# fixture.net
KiCad netlist of a schematic drawn in EAGLE
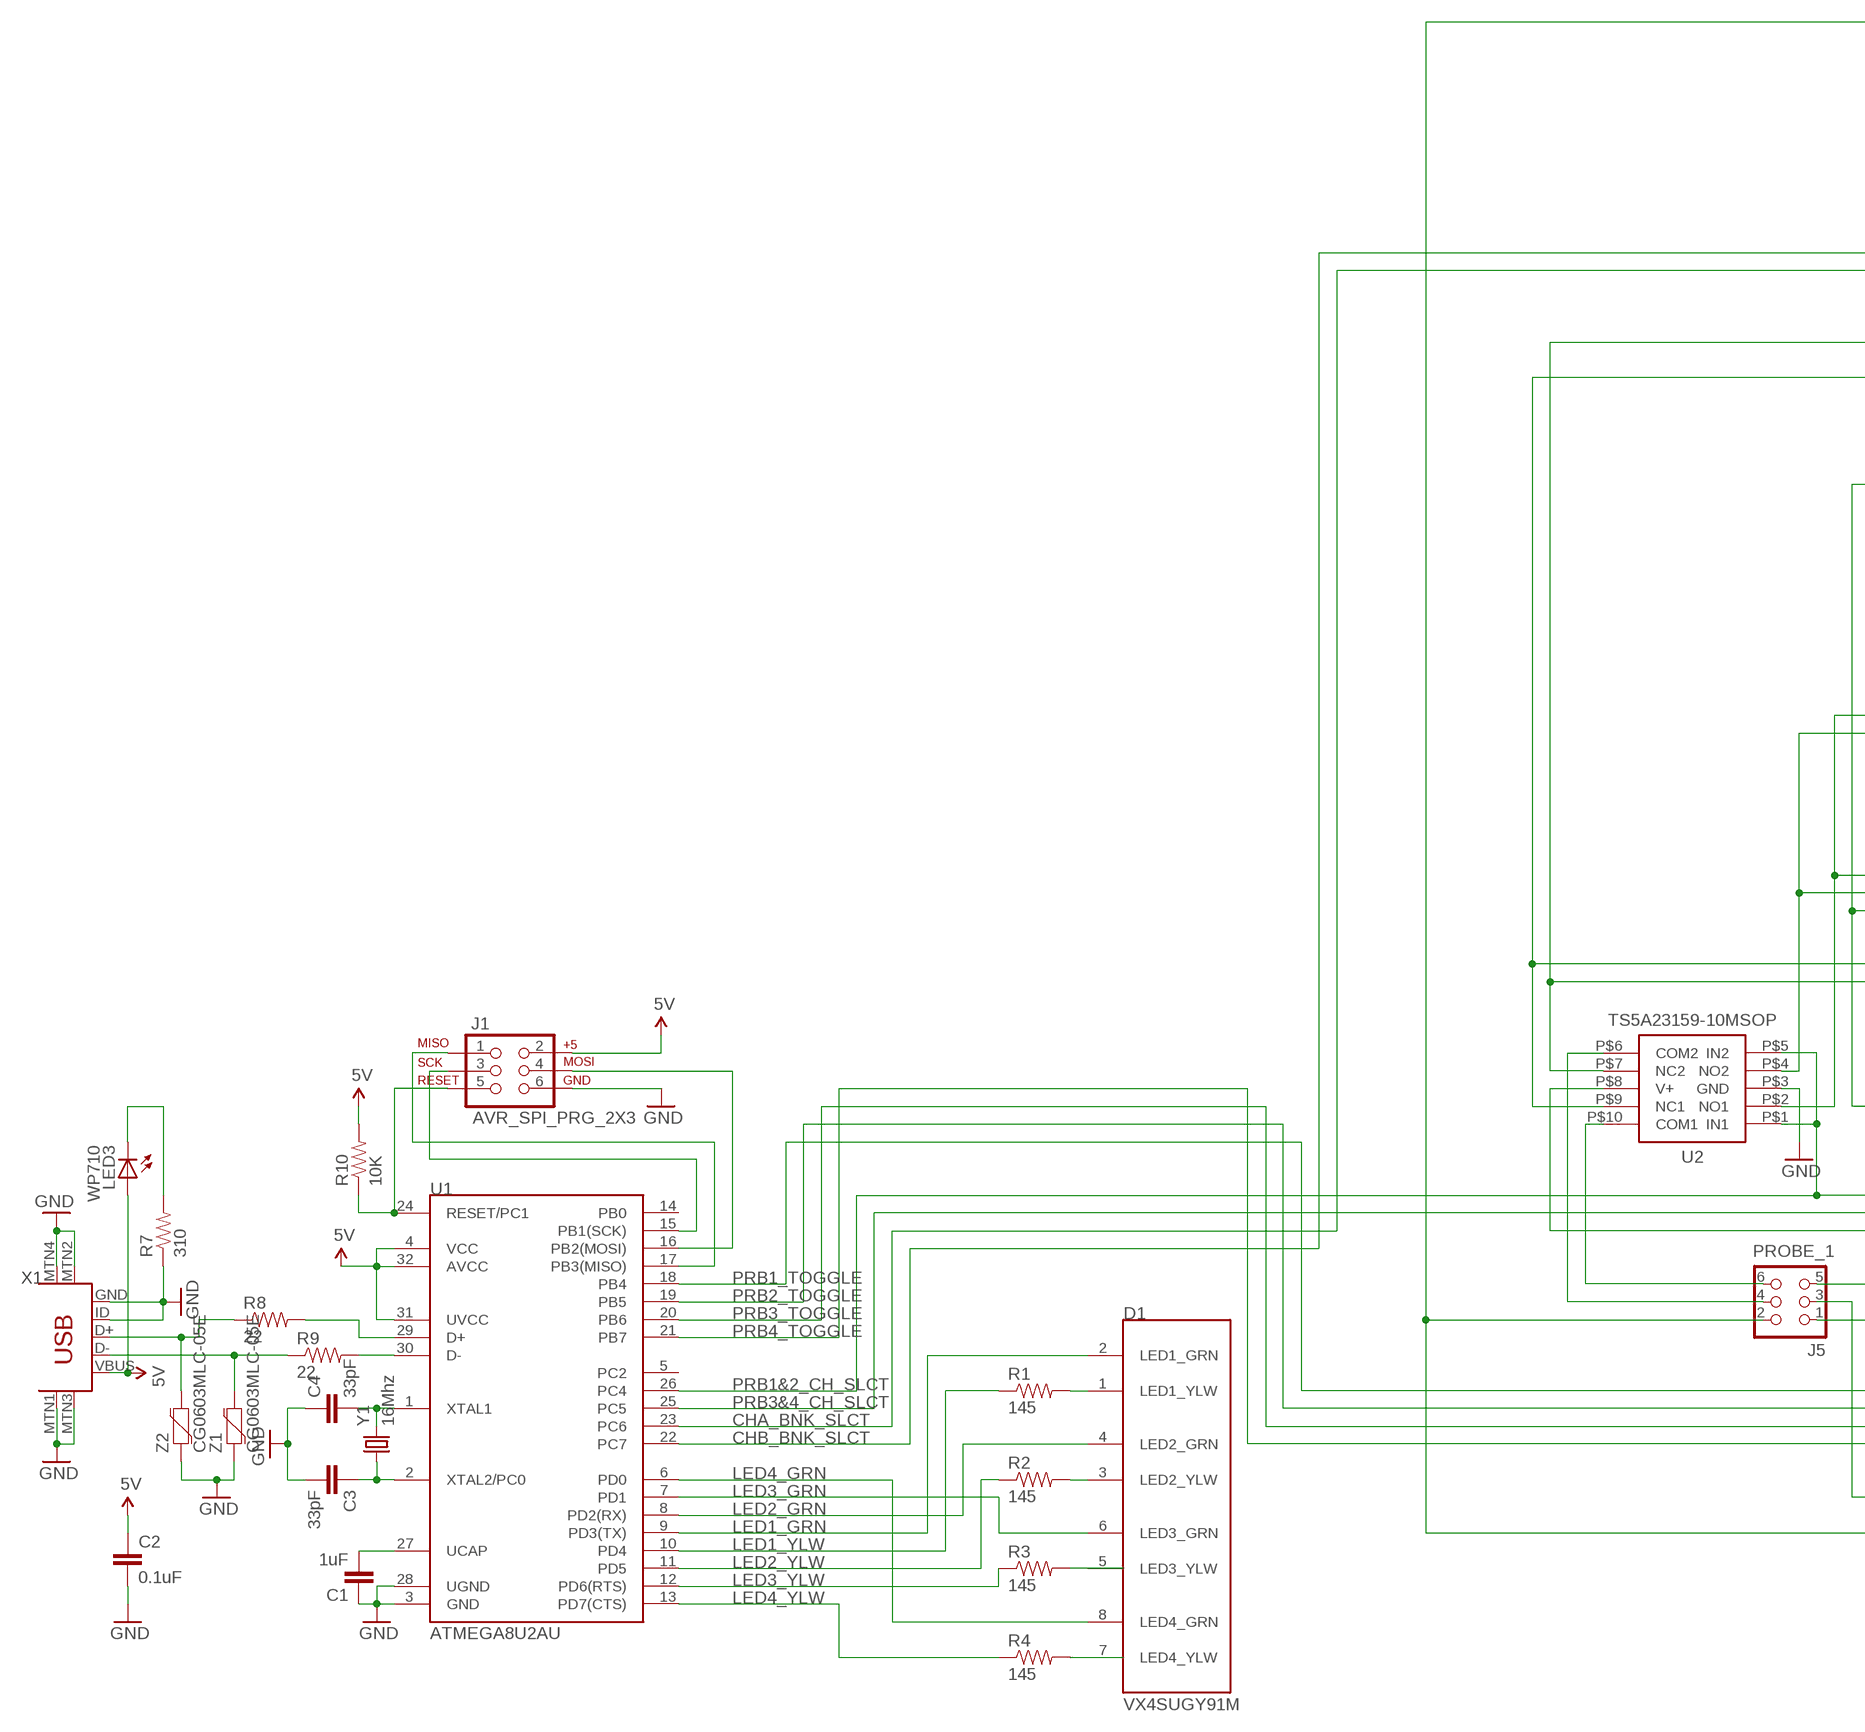
[diagram p0: schematic, sheet 1, part 1 of 2]
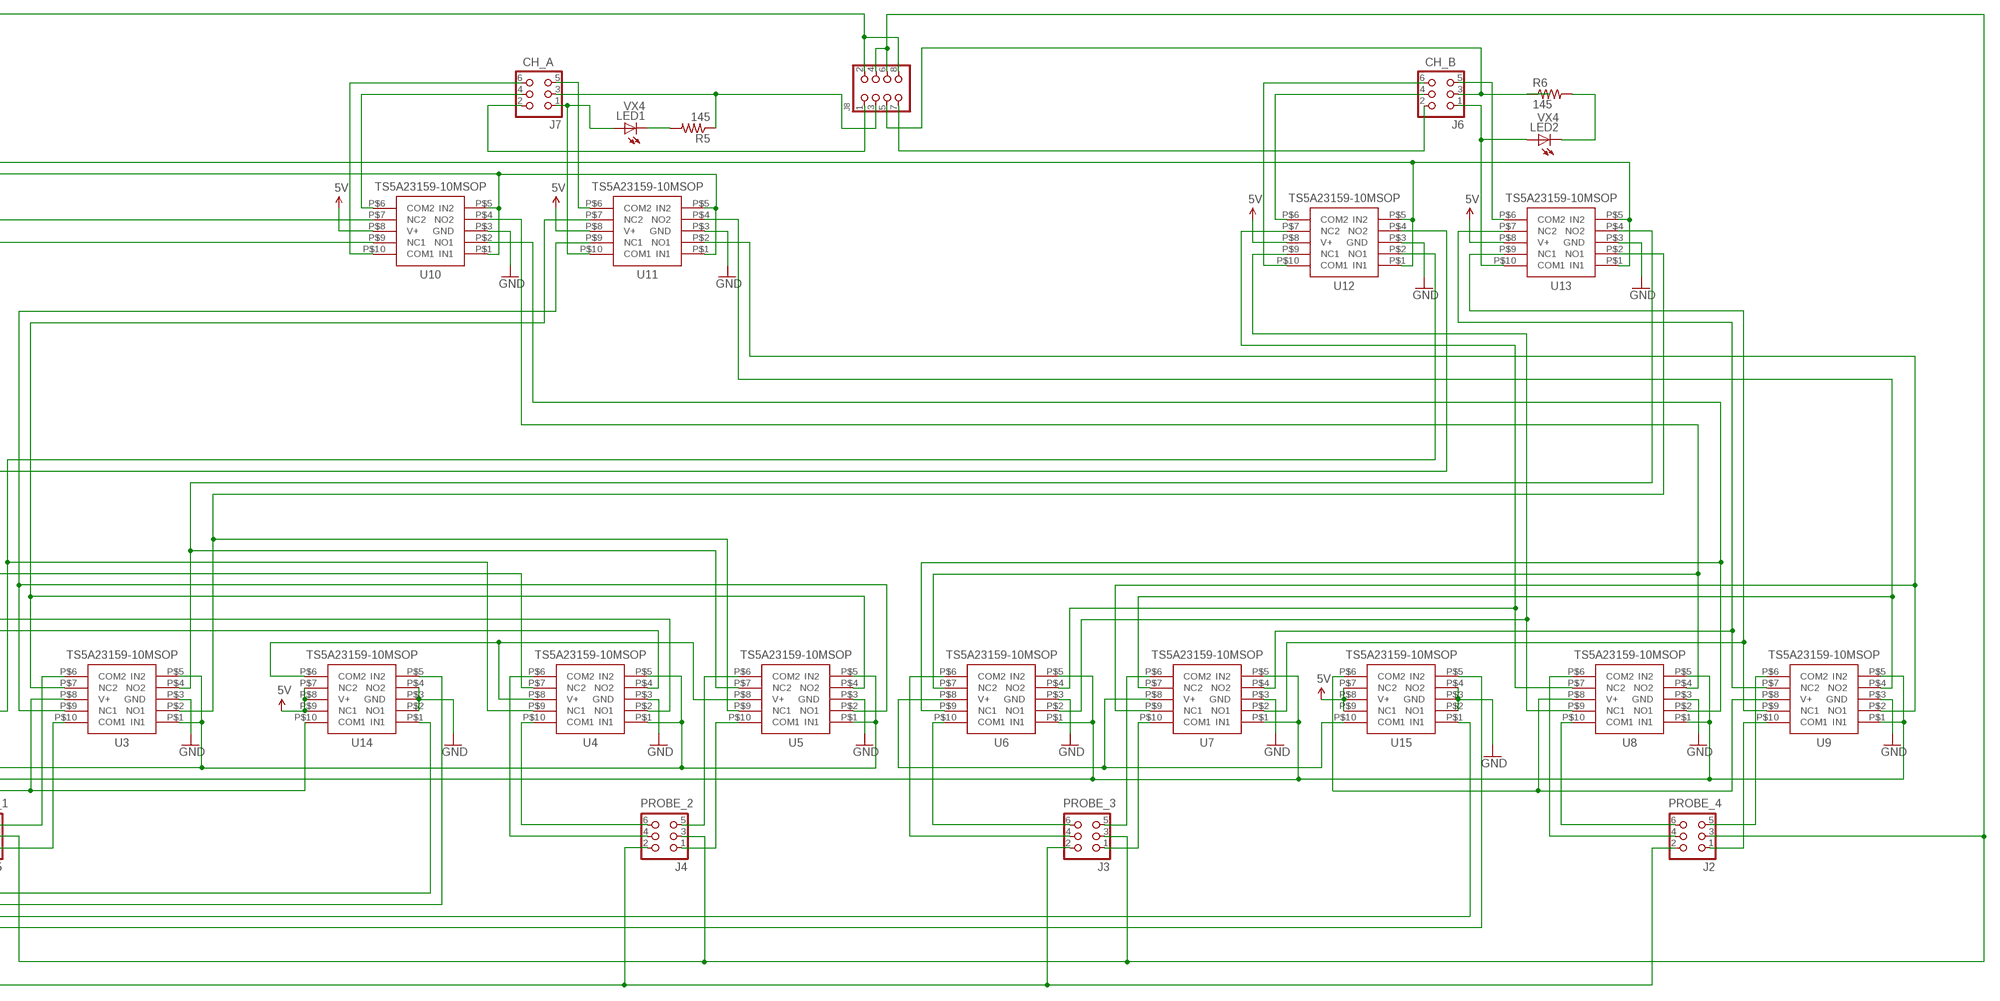
[diagram p1: schematic, sheet 1, part 2 of 2]

(export (version "E")
  (design (tool "Eeschema 10.0.6"))
  (components
    (comp (ref "C1")
      (value "1uF")
      (footprint "eagle-import:0603-CAP")
      (libsource (lib "eagle-import") (part "1.0UF-16V-10%(0603)"))
    )
    (comp (ref "C2")
      (value "0.1uF")
      (footprint "eagle-import:1206")
      (libsource (lib "eagle-import") (part "10UF-6.3V-20%(1206)"))
    )
    (comp (ref "C3")
      (value "33pF")
      (footprint "eagle-import:0603-CAP")
      (libsource (lib "eagle-import") (part "0.1UF-25V(+80/-20%)(0603)"))
    )
    (comp (ref "C4")
      (value "33pF")
      (footprint "eagle-import:0603-CAP")
      (libsource (lib "eagle-import") (part "0.1UF-25V(+80/-20%)(0603)"))
    )
    (comp (ref "D1")
      (value "VX4SUGY91M")
      (footprint "eagle-import:THRU_HOLE")
      (libsource (lib "eagle-import") (part "VX4SUGY91M"))
    )
    (comp (ref "J1")
      (value "AVR_SPI_PRG_2X3")
      (footprint "eagle-import:2X3")
      (libsource (lib "eagle-import") (part "AVR_SPI_PRG_6PTH"))
    )
    (comp (ref "J2")
      (value "CON_HEADER_2X03-PTH")
      (footprint "eagle-import:M2X3")
      (libsource (lib "eagle-import") (part "CON_HEADER_2X03-PTH"))
    )
    (comp (ref "J3")
      (value "CON_HEADER_2X03-PTH")
      (footprint "eagle-import:M2X3")
      (libsource (lib "eagle-import") (part "CON_HEADER_2X03-PTH"))
    )
    (comp (ref "J4")
      (value "CON_HEADER_2X03-PTH")
      (footprint "eagle-import:M2X3")
      (libsource (lib "eagle-import") (part "CON_HEADER_2X03-PTH"))
    )
    (comp (ref "J5")
      (value "CON_HEADER_2X03-PTH")
      (footprint "eagle-import:M2X3")
      (libsource (lib "eagle-import") (part "CON_HEADER_2X03-PTH"))
    )
    (comp (ref "J6")
      (value "CON_HEADER_2X03-PTH")
      (footprint "eagle-import:M2X3")
      (libsource (lib "eagle-import") (part "CON_HEADER_2X03-PTH"))
    )
    (comp (ref "J7")
      (value "CON_HEADER_2X03-PTH")
      (footprint "eagle-import:M2X3")
      (libsource (lib "eagle-import") (part "CON_HEADER_2X03-PTH"))
    )
    (comp (ref "J8")
      (value "CON_HEADER_2X04-PTH")
      (footprint "eagle-import:M2X4")
      (libsource (lib "eagle-import") (part "CON_HEADER_2X04-PTH"))
    )
    (comp (ref "LED1")
      (value "VX4")
      (footprint "eagle-import:LED3MM")
      (libsource (lib "eagle-import") (part "LED3MM"))
    )
    (comp (ref "LED2")
      (value "VX4")
      (footprint "eagle-import:LED3MM")
      (libsource (lib "eagle-import") (part "LED3MM"))
    )
    (comp (ref "LED3")
      (value "WP710")
      (footprint "eagle-import:LED3MM")
      (libsource (lib "eagle-import") (part "LED3MM"))
    )
    (comp (ref "R1")
      (value "145")
      (footprint "eagle-import:0603-RES")
      (libsource (lib "eagle-import") (part "RESISTOR0603-RES"))
    )
    (comp (ref "R2")
      (value "145")
      (footprint "eagle-import:0603-RES")
      (libsource (lib "eagle-import") (part "RESISTOR0603-RES"))
    )
    (comp (ref "R3")
      (value "145")
      (footprint "eagle-import:0603-RES")
      (libsource (lib "eagle-import") (part "RESISTOR0603-RES"))
    )
    (comp (ref "R4")
      (value "145")
      (footprint "eagle-import:0603-RES")
      (libsource (lib "eagle-import") (part "RESISTOR0603-RES"))
    )
    (comp (ref "R5")
      (value "145")
      (footprint "eagle-import:0603-RES")
      (libsource (lib "eagle-import") (part "RESISTOR0603-RES"))
    )
    (comp (ref "R6")
      (value "145")
      (footprint "eagle-import:0603-RES")
      (libsource (lib "eagle-import") (part "RESISTOR0603-RES"))
    )
    (comp (ref "R7")
      (value "310")
      (footprint "eagle-import:0603-RES")
      (libsource (lib "eagle-import") (part "RESISTOR0603-RES"))
    )
    (comp (ref "R8")
      (value "22")
      (footprint "eagle-import:0603-RES")
      (libsource (lib "eagle-import") (part "RESISTOR0603-RES"))
    )
    (comp (ref "R9")
      (value "22")
      (footprint "eagle-import:0603-RES")
      (libsource (lib "eagle-import") (part "RESISTOR0603-RES"))
    )
    (comp (ref "R10")
      (value "10K")
      (footprint "eagle-import:0603-RES")
      (libsource (lib "eagle-import") (part "RESISTOR0603-RES"))
    )
    (comp (ref "U1")
      (value "ATMEGA8U2AU")
      (footprint "eagle-import:TQFP32-08")
      (libsource (lib "eagle-import") (part "ATMEGA8U2AU"))
    )
    (comp (ref "U2")
      (value "TS5A23159-10MSOP")
      (footprint "eagle-import:10MSOP")
      (libsource (lib "eagle-import") (part "TS5A23159-10MSOP"))
    )
    (comp (ref "U3")
      (value "TS5A23159-10MSOP")
      (footprint "eagle-import:10MSOP")
      (libsource (lib "eagle-import") (part "TS5A23159-10MSOP"))
    )
    (comp (ref "U4")
      (value "TS5A23159-10MSOP")
      (footprint "eagle-import:10MSOP")
      (libsource (lib "eagle-import") (part "TS5A23159-10MSOP"))
    )
    (comp (ref "U5")
      (value "TS5A23159-10MSOP")
      (footprint "eagle-import:10MSOP")
      (libsource (lib "eagle-import") (part "TS5A23159-10MSOP"))
    )
    (comp (ref "U6")
      (value "TS5A23159-10MSOP")
      (footprint "eagle-import:10MSOP")
      (libsource (lib "eagle-import") (part "TS5A23159-10MSOP"))
    )
    (comp (ref "U7")
      (value "TS5A23159-10MSOP")
      (footprint "eagle-import:10MSOP")
      (libsource (lib "eagle-import") (part "TS5A23159-10MSOP"))
    )
    (comp (ref "U8")
      (value "TS5A23159-10MSOP")
      (footprint "eagle-import:10MSOP")
      (libsource (lib "eagle-import") (part "TS5A23159-10MSOP"))
    )
    (comp (ref "U9")
      (value "TS5A23159-10MSOP")
      (footprint "eagle-import:10MSOP")
      (libsource (lib "eagle-import") (part "TS5A23159-10MSOP"))
    )
    (comp (ref "U10")
      (value "TS5A23159-10MSOP")
      (footprint "eagle-import:10MSOP")
      (libsource (lib "eagle-import") (part "TS5A23159-10MSOP"))
    )
    (comp (ref "U11")
      (value "TS5A23159-10MSOP")
      (footprint "eagle-import:10MSOP")
      (libsource (lib "eagle-import") (part "TS5A23159-10MSOP"))
    )
    (comp (ref "U12")
      (value "TS5A23159-10MSOP")
      (footprint "eagle-import:10MSOP")
      (libsource (lib "eagle-import") (part "TS5A23159-10MSOP"))
    )
    (comp (ref "U13")
      (value "TS5A23159-10MSOP")
      (footprint "eagle-import:10MSOP")
      (libsource (lib "eagle-import") (part "TS5A23159-10MSOP"))
    )
    (comp (ref "U14")
      (value "TS5A23159-10MSOP")
      (footprint "eagle-import:10MSOP")
      (libsource (lib "eagle-import") (part "TS5A23159-10MSOP"))
    )
    (comp (ref "U15")
      (value "TS5A23159-10MSOP")
      (footprint "eagle-import:10MSOP")
      (libsource (lib "eagle-import") (part "TS5A23159-10MSOP"))
    )
    (comp (ref "X1")
      (value "USB-MINIB-5PIN")
      (footprint "eagle-import:USB-MINIB")
      (libsource (lib "eagle-import") (part "USB-MINIB-5PIN"))
    )
    (comp (ref "Y1")
      (value "16Mhz")
      (footprint "eagle-import:HC49US")
      (libsource (lib "eagle-import") (part "CRYSTALHC49US"))
    )
    (comp (ref "Z1")
      (value "CG0603MLC-05E")
      (footprint "eagle-import:0603-RES")
      (libsource (lib "eagle-import") (part "VARISTOR-0603"))
    )
    (comp (ref "Z2")
      (value "CG0603MLC-05E")
      (footprint "eagle-import:0603-RES")
      (libsource (lib "eagle-import") (part "VARISTOR-0603"))
    )
  )
  (nets
    (net (code "1") (name "/CHA_BNK_SLCT") (class "Default")
      (node (ref "U1") (pin "23") (pinfunction "PC6_23") (pintype "bidirectional"))
      (node (ref "U10") (pin "P$1") (pinfunction "IN1_P$1") (pintype "input"))
      (node (ref "U10") (pin "P$5") (pinfunction "IN2_P$5") (pintype "input"))
      (node (ref "U11") (pin "P$1") (pinfunction "IN1_P$1") (pintype "input"))
      (node (ref "U11") (pin "P$5") (pinfunction "IN2_P$5") (pintype "input"))
    )
    (net (code "2") (name "/CHB_BNK_SLCT") (class "Default")
      (node (ref "U1") (pin "22") (pinfunction "PC7_22") (pintype "bidirectional"))
      (node (ref "U12") (pin "P$1") (pinfunction "IN1_P$1") (pintype "input"))
      (node (ref "U12") (pin "P$5") (pinfunction "IN2_P$5") (pintype "input"))
      (node (ref "U13") (pin "P$1") (pinfunction "IN1_P$1") (pintype "input"))
      (node (ref "U13") (pin "P$5") (pinfunction "IN2_P$5") (pintype "input"))
    )
    (net (code "3") (name "/LED1_GRN") (class "Default")
      (node (ref "D1") (pin "2") (pinfunction "LED1_GRN_2") (pintype "bidirectional"))
      (node (ref "U1") (pin "9") (pinfunction "PD3(TX)_9") (pintype "bidirectional"))
    )
    (net (code "4") (name "/LED1_YLW") (class "Default")
      (node (ref "R1") (pin "1") (pinfunction "1_1") (pintype "passive"))
      (node (ref "U1") (pin "10") (pinfunction "PD4_10") (pintype "bidirectional"))
    )
    (net (code "5") (name "/LED2_GRN") (class "Default")
      (node (ref "D1") (pin "4") (pinfunction "LED2_GRN_4") (pintype "bidirectional"))
      (node (ref "U1") (pin "8") (pinfunction "PD2(RX)_8") (pintype "bidirectional"))
    )
    (net (code "6") (name "/LED2_YLW") (class "Default")
      (node (ref "R2") (pin "1") (pinfunction "1_1") (pintype "passive"))
      (node (ref "U1") (pin "11") (pinfunction "PD5_11") (pintype "bidirectional"))
    )
    (net (code "7") (name "/LED3_GRN") (class "Default")
      (node (ref "D1") (pin "6") (pinfunction "LED3_GRN_6") (pintype "bidirectional"))
      (node (ref "U1") (pin "7") (pinfunction "PD1_7") (pintype "bidirectional"))
    )
    (net (code "8") (name "/LED3_YLW") (class "Default")
      (node (ref "R3") (pin "1") (pinfunction "1_1") (pintype "passive"))
      (node (ref "U1") (pin "12") (pinfunction "PD6(RTS)_12") (pintype "bidirectional"))
    )
    (net (code "9") (name "/LED4_GRN") (class "Default")
      (node (ref "D1") (pin "8") (pinfunction "LED4_GRN_8") (pintype "bidirectional"))
      (node (ref "U1") (pin "6") (pinfunction "PD0_6") (pintype "bidirectional"))
    )
    (net (code "10") (name "/LED4_YLW") (class "Default")
      (node (ref "R4") (pin "1") (pinfunction "1_1") (pintype "passive"))
      (node (ref "U1") (pin "13") (pinfunction "PD7(CTS)_13") (pintype "bidirectional"))
    )
    (net (code "11") (name "/PRB1&2_CH_SLCT") (class "Default")
      (node (ref "U1") (pin "26") (pinfunction "PC4_26") (pintype "bidirectional"))
      (node (ref "U2") (pin "P$1") (pinfunction "IN1_P$1") (pintype "input"))
      (node (ref "U2") (pin "P$5") (pinfunction "IN2_P$5") (pintype "input"))
      (node (ref "U3") (pin "P$1") (pinfunction "IN1_P$1") (pintype "input"))
      (node (ref "U3") (pin "P$5") (pinfunction "IN2_P$5") (pintype "input"))
      (node (ref "U4") (pin "P$1") (pinfunction "IN1_P$1") (pintype "input"))
      (node (ref "U4") (pin "P$5") (pinfunction "IN2_P$5") (pintype "input"))
      (node (ref "U5") (pin "P$1") (pinfunction "IN1_P$1") (pintype "input"))
      (node (ref "U5") (pin "P$5") (pinfunction "IN2_P$5") (pintype "input"))
    )
    (net (code "12") (name "/PRB1_TOGGLE") (class "Default")
      (node (ref "U1") (pin "18") (pinfunction "PB4_18") (pintype "bidirectional"))
      (node (ref "U14") (pin "P$1") (pinfunction "IN1_P$1") (pintype "input"))
    )
    (net (code "13") (name "/PRB2_TOGGLE") (class "Default")
      (node (ref "U1") (pin "19") (pinfunction "PB5_19") (pintype "bidirectional"))
      (node (ref "U14") (pin "P$5") (pinfunction "IN2_P$5") (pintype "input"))
    )
    (net (code "14") (name "/PRB3&4_CH_SLCT") (class "Default")
      (node (ref "U1") (pin "25") (pinfunction "PC5_25") (pintype "bidirectional"))
      (node (ref "U6") (pin "P$1") (pinfunction "IN1_P$1") (pintype "input"))
      (node (ref "U6") (pin "P$5") (pinfunction "IN2_P$5") (pintype "input"))
      (node (ref "U7") (pin "P$1") (pinfunction "IN1_P$1") (pintype "input"))
      (node (ref "U7") (pin "P$5") (pinfunction "IN2_P$5") (pintype "input"))
      (node (ref "U8") (pin "P$1") (pinfunction "IN1_P$1") (pintype "input"))
      (node (ref "U8") (pin "P$5") (pinfunction "IN2_P$5") (pintype "input"))
      (node (ref "U9") (pin "P$1") (pinfunction "IN1_P$1") (pintype "input"))
      (node (ref "U9") (pin "P$5") (pinfunction "IN2_P$5") (pintype "input"))
    )
    (net (code "15") (name "/PRB3_TOGGLE") (class "Default")
      (node (ref "U1") (pin "20") (pinfunction "PB6_20") (pintype "bidirectional"))
      (node (ref "U15") (pin "P$1") (pinfunction "IN1_P$1") (pintype "input"))
    )
    (net (code "16") (name "/PRB4_TOGGLE") (class "Default")
      (node (ref "U1") (pin "21") (pinfunction "PB7_21") (pintype "bidirectional"))
      (node (ref "U15") (pin "P$5") (pinfunction "IN2_P$5") (pintype "input"))
    )
    (net (code "17") (name "5V") (class "Default")
      (node (ref "C2") (pin "1") (pinfunction "1_1") (pintype "passive"))
      (node (ref "J1") (pin "2") (pinfunction "2_2") (pintype "passive"))
      (node (ref "LED3") (pin "A") (pinfunction "A_A") (pintype "passive"))
      (node (ref "R10") (pin "2") (pinfunction "2_2") (pintype "passive"))
      (node (ref "U1") (pin "31") (pinfunction "UVCC_31") (pintype "bidirectional"))
      (node (ref "U1") (pin "32") (pinfunction "AVCC_32") (pintype "bidirectional"))
      (node (ref "U1") (pin "4") (pinfunction "VCC_4") (pintype "bidirectional"))
      (node (ref "U10") (pin "P$8") (pinfunction "V+_P$8") (pintype "power_in"))
      (node (ref "U11") (pin "P$8") (pinfunction "V+_P$8") (pintype "power_in"))
      (node (ref "U12") (pin "P$8") (pinfunction "V+_P$8") (pintype "power_in"))
      (node (ref "U13") (pin "P$8") (pinfunction "V+_P$8") (pintype "power_in"))
      (node (ref "U14") (pin "P$7") (pinfunction "NC2_P$7") (pintype "bidirectional"))
      (node (ref "U14") (pin "P$8") (pinfunction "V+_P$8") (pintype "power_in"))
      (node (ref "U14") (pin "P$9") (pinfunction "NC1_P$9") (pintype "bidirectional"))
      (node (ref "U15") (pin "P$7") (pinfunction "NC2_P$7") (pintype "bidirectional"))
      (node (ref "U15") (pin "P$8") (pinfunction "V+_P$8") (pintype "power_in"))
      (node (ref "U15") (pin "P$9") (pinfunction "NC1_P$9") (pintype "bidirectional"))
      (node (ref "X1") (pin "VBUS") (pinfunction "VBUS_VBUS") (pintype "bidirectional"))
    )
    (net (code "18") (name "GND") (class "Default")
      (node (ref "C1") (pin "1") (pinfunction "1_1") (pintype "passive"))
      (node (ref "C2") (pin "2") (pinfunction "2_2") (pintype "passive"))
      (node (ref "C3") (pin "2") (pinfunction "2_2") (pintype "passive"))
      (node (ref "C4") (pin "1") (pinfunction "1_1") (pintype "passive"))
      (node (ref "J1") (pin "6") (pinfunction "6_6") (pintype "passive"))
      (node (ref "R7") (pin "1") (pinfunction "1_1") (pintype "passive"))
      (node (ref "U1") (pin "28") (pinfunction "UGND_28") (pintype "bidirectional"))
      (node (ref "U1") (pin "3") (pinfunction "GND_3") (pintype "bidirectional"))
      (node (ref "U10") (pin "P$3") (pinfunction "GND_P$3") (pintype "power_in"))
      (node (ref "U11") (pin "P$3") (pinfunction "GND_P$3") (pintype "power_in"))
      (node (ref "U12") (pin "P$3") (pinfunction "GND_P$3") (pintype "power_in"))
      (node (ref "U13") (pin "P$3") (pinfunction "GND_P$3") (pintype "power_in"))
      (node (ref "U14") (pin "P$2") (pinfunction "NO1_P$2") (pintype "bidirectional"))
      (node (ref "U14") (pin "P$3") (pinfunction "GND_P$3") (pintype "power_in"))
      (node (ref "U14") (pin "P$4") (pinfunction "NO2_P$4") (pintype "bidirectional"))
      (node (ref "U15") (pin "P$2") (pinfunction "NO1_P$2") (pintype "bidirectional"))
      (node (ref "U15") (pin "P$3") (pinfunction "GND_P$3") (pintype "power_in"))
      (node (ref "U15") (pin "P$4") (pinfunction "NO2_P$4") (pintype "bidirectional"))
      (node (ref "U2") (pin "P$3") (pinfunction "GND_P$3") (pintype "power_in"))
      (node (ref "U3") (pin "P$3") (pinfunction "GND_P$3") (pintype "power_in"))
      (node (ref "U4") (pin "P$3") (pinfunction "GND_P$3") (pintype "power_in"))
      (node (ref "U5") (pin "P$3") (pinfunction "GND_P$3") (pintype "power_in"))
      (node (ref "U6") (pin "P$3") (pinfunction "GND_P$3") (pintype "power_in"))
      (node (ref "U7") (pin "P$3") (pinfunction "GND_P$3") (pintype "power_in"))
      (node (ref "U8") (pin "P$3") (pinfunction "GND_P$3") (pintype "power_in"))
      (node (ref "U9") (pin "P$3") (pinfunction "GND_P$3") (pintype "power_in"))
      (node (ref "X1") (pin "GND") (pinfunction "GND_GND") (pintype "bidirectional"))
      (node (ref "X1") (pin "ID") (pinfunction "ID_ID") (pintype "bidirectional"))
      (node (ref "X1") (pin "MTN1") (pinfunction "MTN2_MTN1") (pintype "bidirectional"))
      (node (ref "X1") (pin "MTN2") (pinfunction "MTN3_MTN2") (pintype "bidirectional"))
      (node (ref "X1") (pin "MTN3") (pinfunction "MTN1_MTN3") (pintype "bidirectional"))
      (node (ref "X1") (pin "MTN4") (pinfunction "MTN4_MTN4") (pintype "bidirectional"))
      (node (ref "Z1") (pin "1") (pinfunction "1_1") (pintype "passive"))
      (node (ref "Z2") (pin "1") (pinfunction "1_1") (pintype "passive"))
    )
    (net (code "19") (name "Net-(D1-LED1_YLW)") (class "Default")
      (node (ref "D1") (pin "1") (pinfunction "LED1_YLW_1") (pintype "bidirectional"))
      (node (ref "R1") (pin "2") (pinfunction "2_2") (pintype "passive"))
    )
    (net (code "20") (name "Net-(D1-LED2_YLW)") (class "Default")
      (node (ref "D1") (pin "3") (pinfunction "LED2_YLW_3") (pintype "bidirectional"))
      (node (ref "R2") (pin "2") (pinfunction "2_2") (pintype "passive"))
    )
    (net (code "21") (name "Net-(D1-LED3_YLW)") (class "Default")
      (node (ref "D1") (pin "5") (pinfunction "LED3_YLW_5") (pintype "bidirectional"))
      (node (ref "R3") (pin "2") (pinfunction "2_2") (pintype "passive"))
    )
    (net (code "22") (name "Net-(D1-LED4_YLW)") (class "Default")
      (node (ref "D1") (pin "7") (pinfunction "LED4_YLW_7") (pintype "bidirectional"))
      (node (ref "R4") (pin "2") (pinfunction "2_2") (pintype "passive"))
    )
    (net (code "23") (name "Net-(J8-P$1)") (class "Default")
      (node (ref "J7") (pin "2") (pinfunction "2_2") (pintype "passive"))
      (node (ref "J8") (pin "1") (pinfunction "P$1_1") (pintype "passive"))
    )
    (net (code "24") (name "Net-(J8-P$2)") (class "Default")
      (node (ref "J2") (pin "2") (pinfunction "2_2") (pintype "passive"))
      (node (ref "J3") (pin "2") (pinfunction "2_2") (pintype "passive"))
      (node (ref "J4") (pin "2") (pinfunction "2_2") (pintype "passive"))
      (node (ref "J5") (pin "2") (pinfunction "2_2") (pintype "passive"))
      (node (ref "J8") (pin "2") (pinfunction "P$2_2") (pintype "passive"))
      (node (ref "J8") (pin "8") (pinfunction "P$8_8") (pintype "passive"))
    )
    (net (code "25") (name "Net-(J8-P$3)") (class "Default")
      (node (ref "J7") (pin "3") (pinfunction "3_3") (pintype "passive"))
      (node (ref "J8") (pin "3") (pinfunction "P$3_3") (pintype "passive"))
      (node (ref "R5") (pin "1") (pinfunction "1_1") (pintype "passive"))
    )
    (net (code "26") (name "Net-(J8-P$4)") (class "Default")
      (node (ref "J2") (pin "3") (pinfunction "3_3") (pintype "passive"))
      (node (ref "J3") (pin "3") (pinfunction "3_3") (pintype "passive"))
      (node (ref "J4") (pin "3") (pinfunction "3_3") (pintype "passive"))
      (node (ref "J5") (pin "3") (pinfunction "3_3") (pintype "passive"))
      (node (ref "J8") (pin "4") (pinfunction "P$4_4") (pintype "passive"))
      (node (ref "J8") (pin "6") (pinfunction "P$6_6") (pintype "passive"))
    )
    (net (code "27") (name "Net-(J8-P$5)") (class "Default")
      (node (ref "J6") (pin "3") (pinfunction "3_3") (pintype "passive"))
      (node (ref "J8") (pin "5") (pinfunction "P$5_5") (pintype "passive"))
      (node (ref "R6") (pin "1") (pinfunction "1_1") (pintype "passive"))
    )
    (net (code "28") (name "Net-(J8-P$7)") (class "Default")
      (node (ref "J6") (pin "2") (pinfunction "2_2") (pintype "passive"))
      (node (ref "J8") (pin "7") (pinfunction "P$7_7") (pintype "passive"))
    )
    (net (code "29") (name "Net-(LED1-C)") (class "Default")
      (node (ref "LED1") (pin "K") (pinfunction "C_K") (pintype "passive"))
      (node (ref "R5") (pin "2") (pinfunction "2_2") (pintype "passive"))
    )
    (net (code "30") (name "Net-(LED2-C)") (class "Default")
      (node (ref "LED2") (pin "K") (pinfunction "C_K") (pintype "passive"))
      (node (ref "R6") (pin "2") (pinfunction "2_2") (pintype "passive"))
    )
    (net (code "31") (name "Net-(LED3-C)") (class "Default")
      (node (ref "LED3") (pin "K") (pinfunction "C_K") (pintype "passive"))
      (node (ref "R7") (pin "2") (pinfunction "2_2") (pintype "passive"))
    )
    (net (code "32") (name "Net-(R8-Pad1)") (class "Default")
      (node (ref "R8") (pin "1") (pinfunction "1_1") (pintype "passive"))
      (node (ref "X1") (pin "D+") (pinfunction "D+_D+") (pintype "bidirectional"))
      (node (ref "Z2") (pin "2") (pinfunction "2_2") (pintype "passive"))
    )
    (net (code "33") (name "Net-(R9-Pad1)") (class "Default")
      (node (ref "R9") (pin "1") (pinfunction "1_1") (pintype "passive"))
      (node (ref "X1") (pin "D-") (pinfunction "D-_D-") (pintype "bidirectional"))
      (node (ref "Z1") (pin "2") (pinfunction "2_2") (pintype "passive"))
    )
    (net (code "34") (name "Net-(U1-D+)") (class "Default")
      (node (ref "R8") (pin "2") (pinfunction "2_2") (pintype "passive"))
      (node (ref "U1") (pin "29") (pinfunction "D+_29") (pintype "bidirectional"))
    )
    (net (code "35") (name "Net-(U1-D-)") (class "Default")
      (node (ref "R9") (pin "2") (pinfunction "2_2") (pintype "passive"))
      (node (ref "U1") (pin "30") (pinfunction "D-_30") (pintype "bidirectional"))
    )
    (net (code "36") (name "Net-(U1-PB1(SCK))") (class "Default")
      (node (ref "J1") (pin "3") (pinfunction "3_3") (pintype "passive"))
      (node (ref "U1") (pin "15") (pinfunction "PB1(SCK)_15") (pintype "bidirectional"))
    )
    (net (code "37") (name "Net-(U1-PB2(MOSI))") (class "Default")
      (node (ref "J1") (pin "4") (pinfunction "4_4") (pintype "passive"))
      (node (ref "U1") (pin "16") (pinfunction "PB2(MOSI)_16") (pintype "bidirectional"))
    )
    (net (code "38") (name "Net-(U1-PB3(MISO))") (class "Default")
      (node (ref "J1") (pin "1") (pinfunction "1_1") (pintype "passive"))
      (node (ref "U1") (pin "17") (pinfunction "PB3(MISO)_17") (pintype "bidirectional"))
    )
    (net (code "39") (name "Net-(U1-RESET{slash}PC1)") (class "Default")
      (node (ref "J1") (pin "5") (pinfunction "5_5") (pintype "passive"))
      (node (ref "R10") (pin "1") (pinfunction "1_1") (pintype "passive"))
      (node (ref "U1") (pin "24") (pinfunction "RESET/PC1_24") (pintype "bidirectional"))
    )
    (net (code "40") (name "Net-(U1-UCAP)") (class "Default")
      (node (ref "C1") (pin "2") (pinfunction "2_2") (pintype "passive"))
      (node (ref "U1") (pin "27") (pinfunction "UCAP_27") (pintype "bidirectional"))
    )
    (net (code "41") (name "Net-(U1-XTAL1)") (class "Default")
      (node (ref "C4") (pin "2") (pinfunction "2_2") (pintype "passive"))
      (node (ref "U1") (pin "1") (pinfunction "XTAL1_1") (pintype "bidirectional"))
      (node (ref "Y1") (pin "2") (pinfunction "2_2") (pintype "passive"))
    )
    (net (code "42") (name "Net-(U1-XTAL2{slash}PC0)") (class "Default")
      (node (ref "C3") (pin "1") (pinfunction "1_1") (pintype "passive"))
      (node (ref "U1") (pin "2") (pinfunction "XTAL2/PC0_2") (pintype "bidirectional"))
      (node (ref "Y1") (pin "1") (pinfunction "1_1") (pintype "passive"))
    )
    (net (code "43") (name "Net-(U2-COM1)") (class "Default")
      (node (ref "J5") (pin "6") (pinfunction "6_6") (pintype "passive"))
      (node (ref "U2") (pin "P$10") (pinfunction "COM1_P$10") (pintype "bidirectional"))
    )
    (net (code "44") (name "Net-(U2-COM2)") (class "Default")
      (node (ref "J5") (pin "4") (pinfunction "4_4") (pintype "passive"))
      (node (ref "U2") (pin "P$6") (pinfunction "COM2_P$6") (pintype "bidirectional"))
    )
    (net (code "45") (name "Net-(U3-COM1)") (class "Default")
      (node (ref "J5") (pin "1") (pinfunction "1_1") (pintype "passive"))
      (node (ref "U3") (pin "P$10") (pinfunction "COM1_P$10") (pintype "bidirectional"))
    )
    (net (code "46") (name "Net-(U3-COM2)") (class "Default")
      (node (ref "J5") (pin "5") (pinfunction "5_5") (pintype "passive"))
      (node (ref "U3") (pin "P$6") (pinfunction "COM2_P$6") (pintype "bidirectional"))
    )
    (net (code "47") (name "Net-(U4-COM1)") (class "Default")
      (node (ref "J4") (pin "6") (pinfunction "6_6") (pintype "passive"))
      (node (ref "U4") (pin "P$10") (pinfunction "COM1_P$10") (pintype "bidirectional"))
    )
    (net (code "48") (name "Net-(U4-COM2)") (class "Default")
      (node (ref "J4") (pin "4") (pinfunction "4_4") (pintype "passive"))
      (node (ref "U4") (pin "P$6") (pinfunction "COM2_P$6") (pintype "bidirectional"))
    )
    (net (code "49") (name "Net-(U5-COM1)") (class "Default")
      (node (ref "J4") (pin "1") (pinfunction "1_1") (pintype "passive"))
      (node (ref "U5") (pin "P$10") (pinfunction "COM1_P$10") (pintype "bidirectional"))
    )
    (net (code "50") (name "Net-(U5-COM2)") (class "Default")
      (node (ref "J4") (pin "5") (pinfunction "5_5") (pintype "passive"))
      (node (ref "U5") (pin "P$6") (pinfunction "COM2_P$6") (pintype "bidirectional"))
    )
    (net (code "51") (name "Net-(U6-COM1)") (class "Default")
      (node (ref "J3") (pin "6") (pinfunction "6_6") (pintype "passive"))
      (node (ref "U6") (pin "P$10") (pinfunction "COM1_P$10") (pintype "bidirectional"))
    )
    (net (code "52") (name "Net-(U6-COM2)") (class "Default")
      (node (ref "J3") (pin "4") (pinfunction "4_4") (pintype "passive"))
      (node (ref "U6") (pin "P$6") (pinfunction "COM2_P$6") (pintype "bidirectional"))
    )
    (net (code "53") (name "Net-(U7-COM1)") (class "Default")
      (node (ref "J3") (pin "1") (pinfunction "1_1") (pintype "passive"))
      (node (ref "U7") (pin "P$10") (pinfunction "COM1_P$10") (pintype "bidirectional"))
    )
    (net (code "54") (name "Net-(U7-COM2)") (class "Default")
      (node (ref "J3") (pin "5") (pinfunction "5_5") (pintype "passive"))
      (node (ref "U7") (pin "P$6") (pinfunction "COM2_P$6") (pintype "bidirectional"))
    )
    (net (code "55") (name "Net-(U8-COM1)") (class "Default")
      (node (ref "J2") (pin "6") (pinfunction "6_6") (pintype "passive"))
      (node (ref "U8") (pin "P$10") (pinfunction "COM1_P$10") (pintype "bidirectional"))
    )
    (net (code "56") (name "Net-(U8-COM2)") (class "Default")
      (node (ref "J2") (pin "4") (pinfunction "4_4") (pintype "passive"))
      (node (ref "U8") (pin "P$6") (pinfunction "COM2_P$6") (pintype "bidirectional"))
    )
    (net (code "57") (name "Net-(U9-COM1)") (class "Default")
      (node (ref "J2") (pin "1") (pinfunction "1_1") (pintype "passive"))
      (node (ref "U9") (pin "P$10") (pinfunction "COM1_P$10") (pintype "bidirectional"))
    )
    (net (code "58") (name "Net-(U9-COM2)") (class "Default")
      (node (ref "J2") (pin "5") (pinfunction "5_5") (pintype "passive"))
      (node (ref "U9") (pin "P$6") (pinfunction "COM2_P$6") (pintype "bidirectional"))
    )
    (net (code "59") (name "Net-(U10-COM1)") (class "Default")
      (node (ref "J7") (pin "6") (pinfunction "6_6") (pintype "passive"))
      (node (ref "U10") (pin "P$10") (pinfunction "COM1_P$10") (pintype "bidirectional"))
    )
    (net (code "60") (name "Net-(U10-COM2)") (class "Default")
      (node (ref "J7") (pin "4") (pinfunction "4_4") (pintype "passive"))
      (node (ref "U10") (pin "P$6") (pinfunction "COM2_P$6") (pintype "bidirectional"))
    )
    (net (code "61") (name "Net-(U10-NC1)") (class "Default")
      (node (ref "U10") (pin "P$9") (pinfunction "NC1_P$9") (pintype "bidirectional"))
      (node (ref "U2") (pin "P$9") (pinfunction "NC1_P$9") (pintype "bidirectional"))
      (node (ref "U4") (pin "P$2") (pinfunction "NO1_P$2") (pintype "bidirectional"))
    )
    (net (code "62") (name "Net-(U10-NC2)") (class "Default")
      (node (ref "U10") (pin "P$7") (pinfunction "NC2_P$7") (pintype "bidirectional"))
      (node (ref "U2") (pin "P$7") (pinfunction "NC2_P$7") (pintype "bidirectional"))
      (node (ref "U4") (pin "P$4") (pinfunction "NO2_P$4") (pintype "bidirectional"))
    )
    (net (code "63") (name "Net-(U10-NO1)") (class "Default")
      (node (ref "U10") (pin "P$2") (pinfunction "NO1_P$2") (pintype "bidirectional"))
      (node (ref "U6") (pin "P$9") (pinfunction "NC1_P$9") (pintype "bidirectional"))
      (node (ref "U8") (pin "P$2") (pinfunction "NO1_P$2") (pintype "bidirectional"))
    )
    (net (code "64") (name "Net-(U10-NO2)") (class "Default")
      (node (ref "U10") (pin "P$4") (pinfunction "NO2_P$4") (pintype "bidirectional"))
      (node (ref "U6") (pin "P$7") (pinfunction "NC2_P$7") (pintype "bidirectional"))
      (node (ref "U8") (pin "P$4") (pinfunction "NO2_P$4") (pintype "bidirectional"))
    )
    (net (code "65") (name "Net-(U11-COM1)") (class "Default")
      (node (ref "J7") (pin "1") (pinfunction "1_1") (pintype "passive"))
      (node (ref "LED1") (pin "A") (pinfunction "A_A") (pintype "passive"))
      (node (ref "U11") (pin "P$10") (pinfunction "COM1_P$10") (pintype "bidirectional"))
    )
    (net (code "66") (name "Net-(U11-COM2)") (class "Default")
      (node (ref "J7") (pin "5") (pinfunction "5_5") (pintype "passive"))
      (node (ref "U11") (pin "P$6") (pinfunction "COM2_P$6") (pintype "bidirectional"))
    )
    (net (code "67") (name "Net-(U11-NC1)") (class "Default")
      (node (ref "U11") (pin "P$9") (pinfunction "NC1_P$9") (pintype "bidirectional"))
      (node (ref "U3") (pin "P$9") (pinfunction "NC1_P$9") (pintype "bidirectional"))
      (node (ref "U5") (pin "P$2") (pinfunction "NO1_P$2") (pintype "bidirectional"))
    )
    (net (code "68") (name "Net-(U11-NC2)") (class "Default")
      (node (ref "U11") (pin "P$7") (pinfunction "NC2_P$7") (pintype "bidirectional"))
      (node (ref "U3") (pin "P$7") (pinfunction "NC2_P$7") (pintype "bidirectional"))
      (node (ref "U5") (pin "P$4") (pinfunction "NO2_P$4") (pintype "bidirectional"))
    )
    (net (code "69") (name "Net-(U11-NO1)") (class "Default")
      (node (ref "U11") (pin "P$2") (pinfunction "NO1_P$2") (pintype "bidirectional"))
      (node (ref "U7") (pin "P$9") (pinfunction "NC1_P$9") (pintype "bidirectional"))
      (node (ref "U9") (pin "P$2") (pinfunction "NO1_P$2") (pintype "bidirectional"))
    )
    (net (code "70") (name "Net-(U11-NO2)") (class "Default")
      (node (ref "U11") (pin "P$4") (pinfunction "NO2_P$4") (pintype "bidirectional"))
      (node (ref "U7") (pin "P$7") (pinfunction "NC2_P$7") (pintype "bidirectional"))
      (node (ref "U9") (pin "P$4") (pinfunction "NO2_P$4") (pintype "bidirectional"))
    )
    (net (code "71") (name "Net-(U12-COM1)") (class "Default")
      (node (ref "J6") (pin "6") (pinfunction "6_6") (pintype "passive"))
      (node (ref "U12") (pin "P$10") (pinfunction "COM1_P$10") (pintype "bidirectional"))
    )
    (net (code "72") (name "Net-(U12-COM2)") (class "Default")
      (node (ref "J6") (pin "4") (pinfunction "4_4") (pintype "passive"))
      (node (ref "U12") (pin "P$6") (pinfunction "COM2_P$6") (pintype "bidirectional"))
    )
    (net (code "73") (name "Net-(U12-NC1)") (class "Default")
      (node (ref "U12") (pin "P$9") (pinfunction "NC1_P$9") (pintype "bidirectional"))
      (node (ref "U6") (pin "P$2") (pinfunction "NO1_P$2") (pintype "bidirectional"))
      (node (ref "U8") (pin "P$9") (pinfunction "NC1_P$9") (pintype "bidirectional"))
    )
    (net (code "74") (name "Net-(U12-NC2)") (class "Default")
      (node (ref "U12") (pin "P$7") (pinfunction "NC2_P$7") (pintype "bidirectional"))
      (node (ref "U6") (pin "P$4") (pinfunction "NO2_P$4") (pintype "bidirectional"))
      (node (ref "U8") (pin "P$7") (pinfunction "NC2_P$7") (pintype "bidirectional"))
    )
    (net (code "75") (name "Net-(U12-NO1)") (class "Default")
      (node (ref "U12") (pin "P$2") (pinfunction "NO1_P$2") (pintype "bidirectional"))
      (node (ref "U2") (pin "P$2") (pinfunction "NO1_P$2") (pintype "bidirectional"))
      (node (ref "U4") (pin "P$9") (pinfunction "NC1_P$9") (pintype "bidirectional"))
    )
    (net (code "76") (name "Net-(U12-NO2)") (class "Default")
      (node (ref "U12") (pin "P$4") (pinfunction "NO2_P$4") (pintype "bidirectional"))
      (node (ref "U2") (pin "P$4") (pinfunction "NO2_P$4") (pintype "bidirectional"))
      (node (ref "U4") (pin "P$7") (pinfunction "NC2_P$7") (pintype "bidirectional"))
    )
    (net (code "77") (name "Net-(U13-COM1)") (class "Default")
      (node (ref "J6") (pin "1") (pinfunction "1_1") (pintype "passive"))
      (node (ref "LED2") (pin "A") (pinfunction "A_A") (pintype "passive"))
      (node (ref "U13") (pin "P$10") (pinfunction "COM1_P$10") (pintype "bidirectional"))
    )
    (net (code "78") (name "Net-(U13-COM2)") (class "Default")
      (node (ref "J6") (pin "5") (pinfunction "5_5") (pintype "passive"))
      (node (ref "U13") (pin "P$6") (pinfunction "COM2_P$6") (pintype "bidirectional"))
    )
    (net (code "79") (name "Net-(U13-NC1)") (class "Default")
      (node (ref "U13") (pin "P$9") (pinfunction "NC1_P$9") (pintype "bidirectional"))
      (node (ref "U7") (pin "P$2") (pinfunction "NO1_P$2") (pintype "bidirectional"))
      (node (ref "U9") (pin "P$9") (pinfunction "NC1_P$9") (pintype "bidirectional"))
    )
    (net (code "80") (name "Net-(U13-NC2)") (class "Default")
      (node (ref "U13") (pin "P$7") (pinfunction "NC2_P$7") (pintype "bidirectional"))
      (node (ref "U7") (pin "P$4") (pinfunction "NO2_P$4") (pintype "bidirectional"))
      (node (ref "U9") (pin "P$7") (pinfunction "NC2_P$7") (pintype "bidirectional"))
    )
    (net (code "81") (name "Net-(U13-NO1)") (class "Default")
      (node (ref "U13") (pin "P$2") (pinfunction "NO1_P$2") (pintype "bidirectional"))
      (node (ref "U3") (pin "P$2") (pinfunction "NO1_P$2") (pintype "bidirectional"))
      (node (ref "U5") (pin "P$9") (pinfunction "NC1_P$9") (pintype "bidirectional"))
    )
    (net (code "82") (name "Net-(U13-NO2)") (class "Default")
      (node (ref "U13") (pin "P$4") (pinfunction "NO2_P$4") (pintype "bidirectional"))
      (node (ref "U3") (pin "P$4") (pinfunction "NO2_P$4") (pintype "bidirectional"))
      (node (ref "U5") (pin "P$7") (pinfunction "NC2_P$7") (pintype "bidirectional"))
    )
    (net (code "83") (name "Net-(U14-COM1)") (class "Default")
      (node (ref "U14") (pin "P$10") (pinfunction "COM1_P$10") (pintype "bidirectional"))
      (node (ref "U2") (pin "P$8") (pinfunction "V+_P$8") (pintype "power_in"))
      (node (ref "U3") (pin "P$8") (pinfunction "V+_P$8") (pintype "power_in"))
    )
    (net (code "84") (name "Net-(U14-COM2)") (class "Default")
      (node (ref "U14") (pin "P$6") (pinfunction "COM2_P$6") (pintype "bidirectional"))
      (node (ref "U4") (pin "P$8") (pinfunction "V+_P$8") (pintype "power_in"))
      (node (ref "U5") (pin "P$8") (pinfunction "V+_P$8") (pintype "power_in"))
    )
    (net (code "85") (name "Net-(U15-COM1)") (class "Default")
      (node (ref "U15") (pin "P$10") (pinfunction "COM1_P$10") (pintype "bidirectional"))
      (node (ref "U6") (pin "P$8") (pinfunction "V+_P$8") (pintype "power_in"))
      (node (ref "U7") (pin "P$8") (pinfunction "V+_P$8") (pintype "power_in"))
    )
    (net (code "86") (name "Net-(U15-COM2)") (class "Default")
      (node (ref "U15") (pin "P$6") (pinfunction "COM2_P$6") (pintype "bidirectional"))
      (node (ref "U8") (pin "P$8") (pinfunction "V+_P$8") (pintype "power_in"))
      (node (ref "U9") (pin "P$8") (pinfunction "V+_P$8") (pintype "power_in"))
    )
    (net (code "87") (name "unconnected-(U1-PB0-Pad14)") (class "Default")
      (node (ref "U1") (pin "14") (pinfunction "PB0_14") (pintype "bidirectional"))
    )
    (net (code "88") (name "unconnected-(U1-PC2-Pad5)") (class "Default")
      (node (ref "U1") (pin "5") (pinfunction "PC2_5") (pintype "bidirectional"))
    )
  )
)
